# CONNECTOR_B.net
KiCad netlist of a schematic drawn in Altium Designer
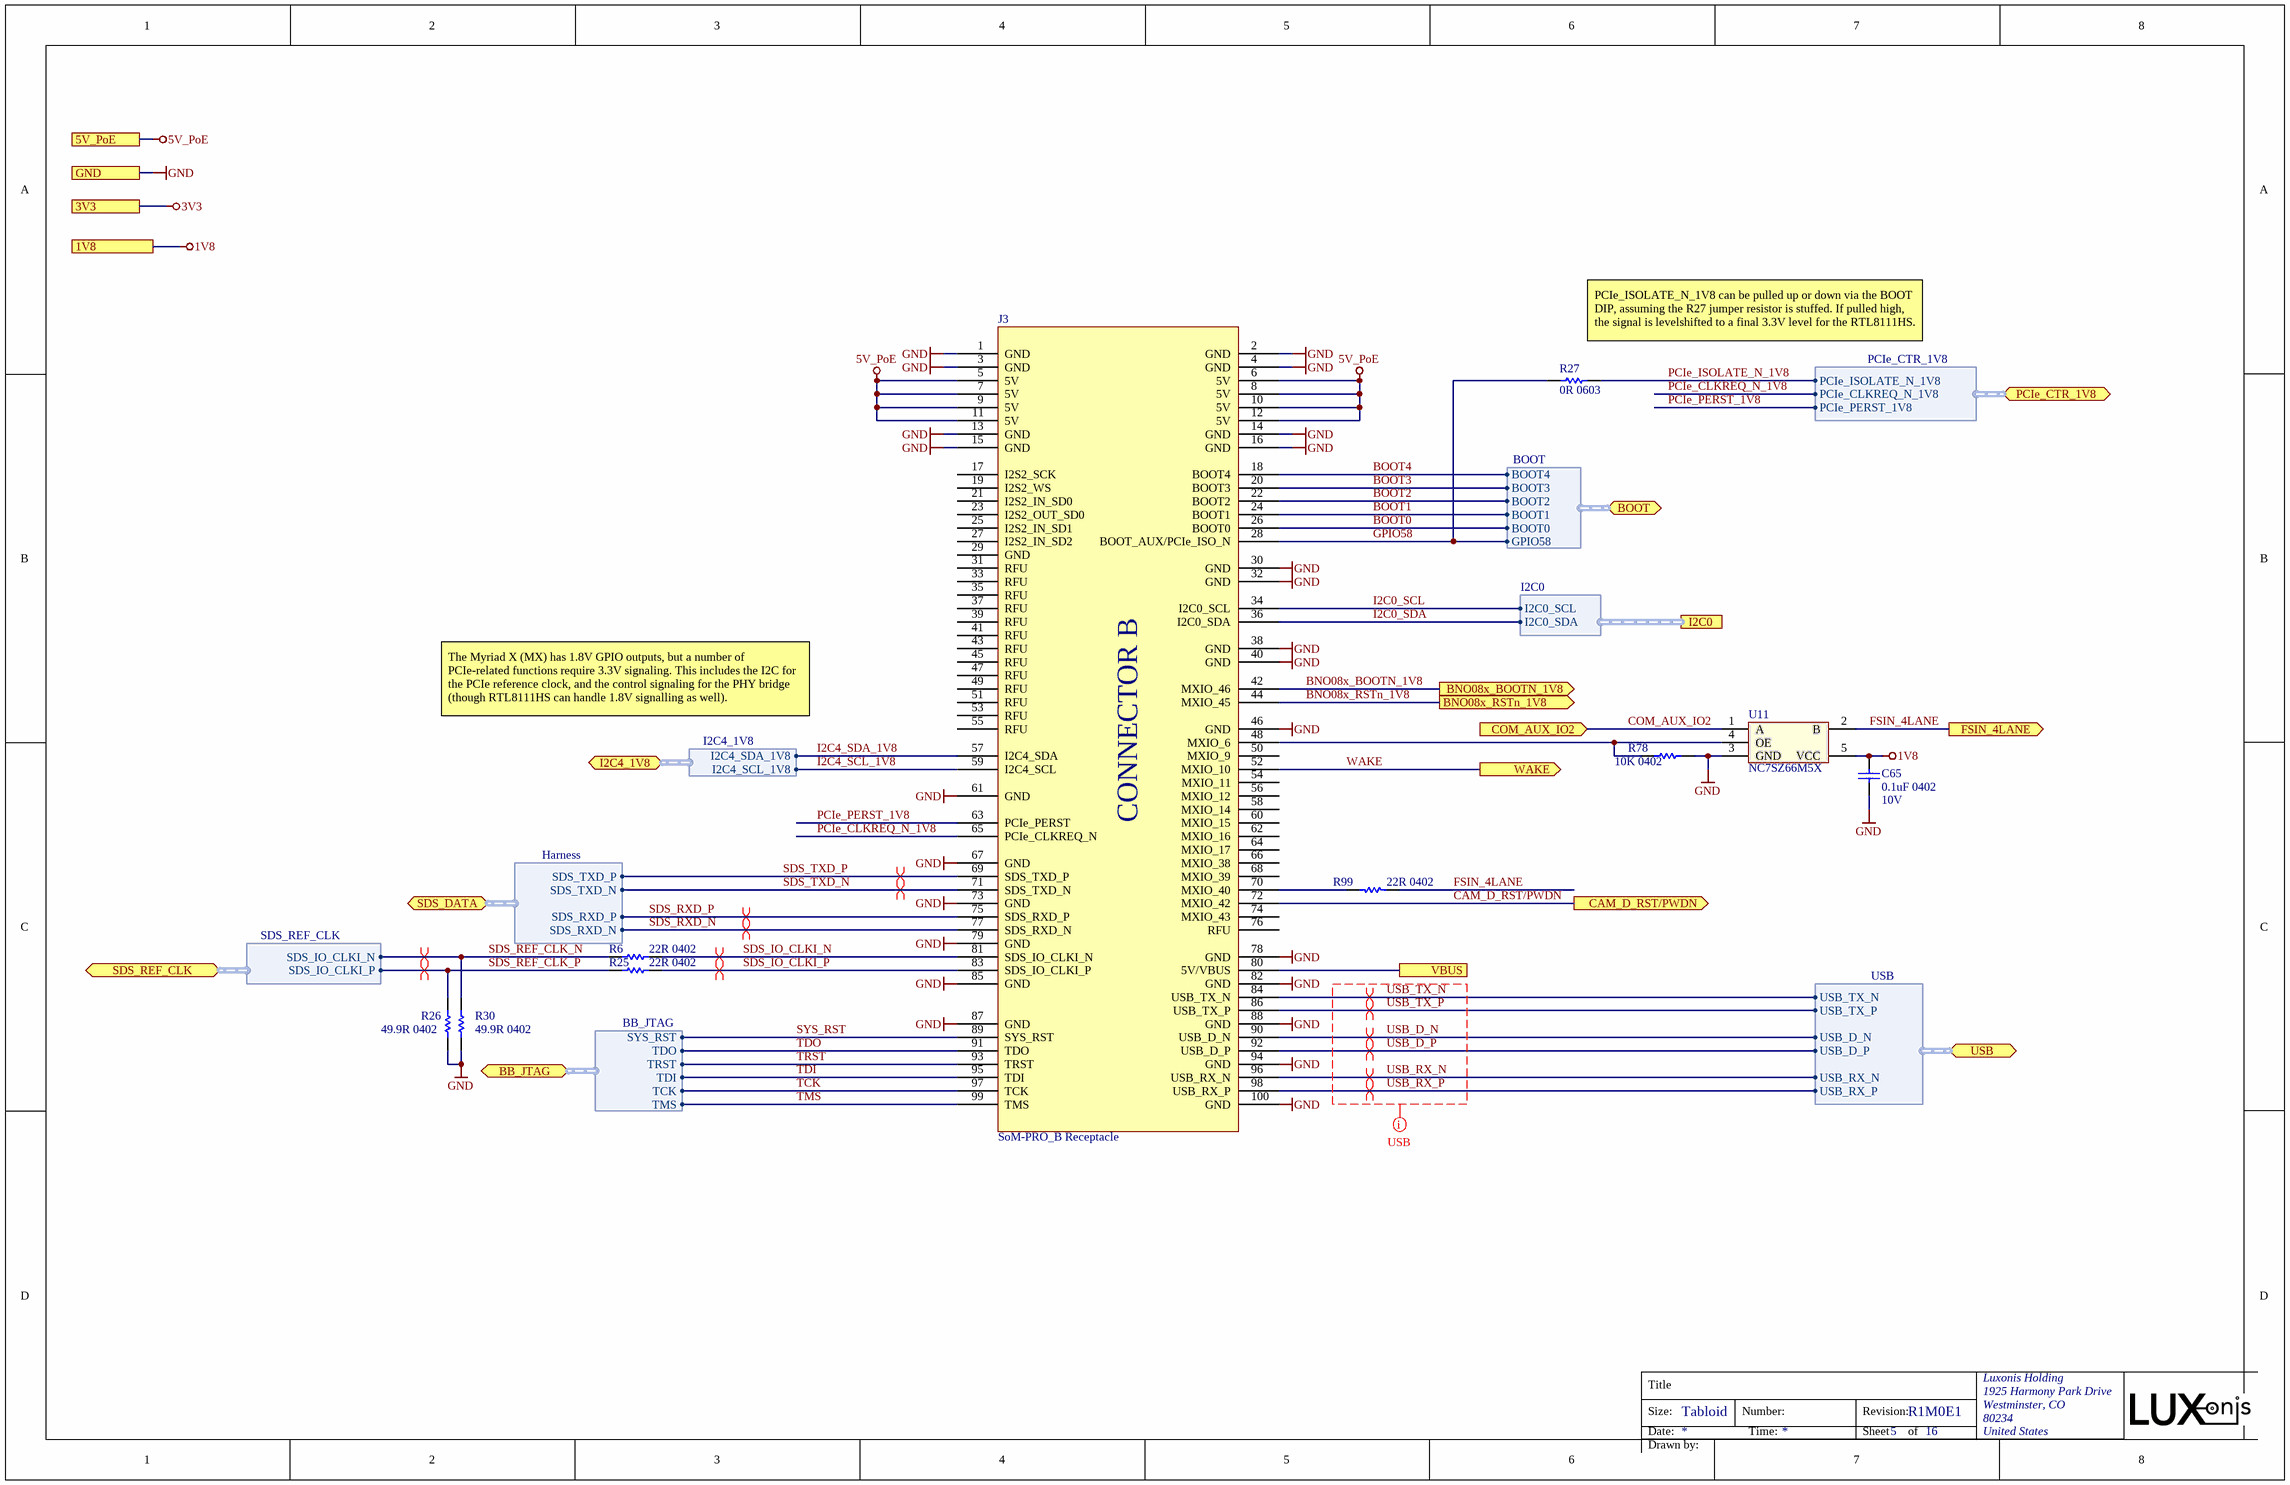
[diagram p0: CONNECTOR_B.SchDoc]

(export (version "E")
  (design (tool "Eeschema 10.0.6"))
  (components
    (comp (ref "C65")
      (value "0.1uF 0402")
      (footprint "CAPC0402(1005)70_L")
      (description "CAP CER 0.1UF 10V X7R 0402 5%")
      (fields (field (name "TOLERANCE") "5%") (field (name "VOLTAGE RATING") "10V"))
      (libsource (lib "LuxonisMaster") (part "GRM155R71A104JA01D"))
    )
    (comp (ref "J3")
      (value "SoM-PRO_B Receptacle")
      (footprint "LuxonisMaster:CON_B_BW2099_SoM_DF40HC-3.0-100DS-0.4V_minpad")
      (description "CONN RCPT 100POS 0.4MM SMD GOLD")
      (libsource (lib "LuxonisMaster") (part "DF40HC(3.0)-100DS-0.4V_SoM-PRO_B"))
    )
    (comp (ref "R6")
      (value "22R 0402")
      (footprint "RES_Altium_Vault_Generic:RESC0402(1005)_L")
      (description "RES SMD 22 OHM 1% 1/16W 0402")
      (fields (field (name "TOLERANCE") "1%"))
      (libsource (lib "BW2098POE") (part "RC0402FR-0722RL"))
    )
    (comp (ref "R25")
      (value "22R 0402")
      (footprint "RES_Altium_Vault_Generic:RESC0402(1005)_L")
      (description "RES SMD 22 OHM 1% 1/16W 0402")
      (fields (field (name "TOLERANCE") "1%"))
      (libsource (lib "BW2098POE") (part "RC0402FR-0722RL"))
    )
    (comp (ref "R26")
      (value "49.9R 0402")
      (footprint "RES_Altium_Vault_Generic:RESC0402(1005)_L")
      (description "RES SMD 49.9 OHM 1% 1/16W 0402")
      (fields (field (name "TOLERANCE") "1%"))
      (libsource (lib "LuxonisMaster") (part "RC0402FR-0749R9L"))
    )
    (comp (ref "R27")
      (value "0R 0603")
      (footprint "RESC0603(1608)_N")
      (fields (field (name "TOLERANCE") "5%"))
      (libsource (lib "LuxonisMaster") (part "CRCW06030000Z0EA"))
    )
    (comp (ref "R30")
      (value "49.9R 0402")
      (footprint "RES_Altium_Vault_Generic:RESC0402(1005)_L")
      (description "RES SMD 49.9 OHM 1% 1/16W 0402")
      (fields (field (name "TOLERANCE") "1%"))
      (libsource (lib "LuxonisMaster") (part "RC0402FR-0749R9L"))
    )
    (comp (ref "R78")
      (value "10K 0402")
      (footprint "RESC0402(1005)_L")
      (fields (field (name "TOLERANCE") "1%"))
      (libsource (lib "LuxonisMaster") (part "RC0402FR-1310KL"))
    )
    (comp (ref "R99")
      (value "22R 0402")
      (footprint "RES_Altium_Vault_Generic:RESC0402(1005)_L")
      (description "RES SMD 22 OHM 1% 1/16W 0402")
      (fields (field (name "TOLERANCE") "1%"))
      (libsource (lib "BW2098POE") (part "RC0402FR-0722RL"))
    )
    (comp (ref "U11")
      (value "NC7SZ66M5X")
      (footprint "SOT235")
      (fields (field (name "VOLTAGE") "5V"))
      (libsource (lib "DD2099_4CAM_FFC") (part "NC7SZ66M5X"))
    )
  )
  (nets
    (net (code "9") (name "/BNO08x_BOOTN_1V8") (class "Default")
      (node (ref "J3") (pin "42") (pinfunction "MXIO_46_42") (pintype "passive"))
    )
    (net (code "10") (name "/BNO08x_RSTn_1V8") (class "Default")
      (node (ref "J3") (pin "44") (pinfunction "MXIO_45_44") (pintype "passive"))
    )
    (net (code "11") (name "/BOOT0") (class "Default")
      (node (ref "J3") (pin "26") (pinfunction "BOOT0_26") (pintype "passive"))
    )
    (net (code "12") (name "/BOOT1") (class "Default")
      (node (ref "J3") (pin "24") (pinfunction "BOOT1_24") (pintype "passive"))
    )
    (net (code "13") (name "/BOOT2") (class "Default")
      (node (ref "J3") (pin "22") (pinfunction "BOOT2_22") (pintype "passive"))
    )
    (net (code "14") (name "/BOOT3") (class "Default")
      (node (ref "J3") (pin "20") (pinfunction "BOOT3_20") (pintype "passive"))
    )
    (net (code "15") (name "/BOOT4") (class "Default")
      (node (ref "J3") (pin "18") (pinfunction "BOOT4_18") (pintype "passive"))
    )
    (net (code "16") (name "/CAM_D_RST{slash}PWDN") (class "Default")
      (node (ref "J3") (pin "72") (pinfunction "MXIO_42_72") (pintype "passive"))
    )
    (net (code "17") (name "/COM_AUX_IO2") (class "Default")
      (node (ref "U11") (pin "1") (pinfunction "A_1") (pintype "passive"))
    )
    (net (code "18") (name "/FSIN_4LANE") (class "Default")
      (node (ref "R99") (pin "1") (pinfunction "1_1") (pintype "passive"))
      (node (ref "U11") (pin "2") (pinfunction "B_2") (pintype "passive"))
    )
    (net (code "19") (name "/GPIO58") (class "Default")
      (node (ref "J3") (pin "28") (pinfunction "BOOT_AUX/PCIe_ISO_N_28") (pintype "passive"))
      (node (ref "R27") (pin "1") (pinfunction "1_1") (pintype "passive"))
    )
    (net (code "20") (name "/I2C0_SCL") (class "Default")
      (node (ref "J3") (pin "34") (pinfunction "I2C0_SCL_34") (pintype "passive"))
    )
    (net (code "21") (name "/I2C0_SDA") (class "Default")
      (node (ref "J3") (pin "36") (pinfunction "I2C0_SDA_36") (pintype "passive"))
    )
    (net (code "22") (name "/I2C4_SCL_1V8") (class "Default")
      (node (ref "J3") (pin "59") (pinfunction "I2C4_SCL_59") (pintype "passive"))
    )
    (net (code "23") (name "/I2C4_SDA_1V8") (class "Default")
      (node (ref "J3") (pin "57") (pinfunction "I2C4_SDA_57") (pintype "passive"))
    )
    (net (code "24") (name "/PCIe_CLKREQ_N_1V8") (class "Default")
      (node (ref "J3") (pin "65") (pinfunction "PCIe_CLKREQ_N_65") (pintype "passive"))
    )
    (net (code "25") (name "/PCIe_ISOLATE_N_1V8") (class "Default")
      (node (ref "R27") (pin "2") (pinfunction "2_2") (pintype "passive"))
    )
    (net (code "26") (name "/PCIe_PERST_1V8") (class "Default")
      (node (ref "J3") (pin "63") (pinfunction "PCIe_PERST_63") (pintype "passive"))
    )
    (net (code "27") (name "/SDS_IO_CLKI_N") (class "Default")
      (node (ref "J3") (pin "81") (pinfunction "SDS_IO_CLKI_N_81") (pintype "passive"))
      (node (ref "R6") (pin "2") (pinfunction "2_2") (pintype "passive"))
    )
    (net (code "28") (name "/SDS_IO_CLKI_P") (class "Default")
      (node (ref "J3") (pin "83") (pinfunction "SDS_IO_CLKI_P_83") (pintype "passive"))
      (node (ref "R25") (pin "2") (pinfunction "2_2") (pintype "passive"))
    )
    (net (code "29") (name "/SDS_REF_CLK_N") (class "Default")
      (node (ref "R30") (pin "1") (pinfunction "1_1") (pintype "passive"))
      (node (ref "R6") (pin "1") (pinfunction "1_1") (pintype "passive"))
    )
    (net (code "30") (name "/SDS_REF_CLK_P") (class "Default")
      (node (ref "R25") (pin "1") (pinfunction "1_1") (pintype "passive"))
      (node (ref "R26") (pin "2") (pinfunction "2_2") (pintype "passive"))
    )
    (net (code "31") (name "/SDS_RXD_N") (class "Default")
      (node (ref "J3") (pin "77") (pinfunction "SDS_RXD_N_77") (pintype "passive"))
    )
    (net (code "32") (name "/SDS_RXD_P") (class "Default")
      (node (ref "J3") (pin "75") (pinfunction "SDS_RXD_P_75") (pintype "passive"))
    )
    (net (code "33") (name "/SDS_TXD_N") (class "Default")
      (node (ref "J3") (pin "71") (pinfunction "SDS_TXD_N_71") (pintype "passive"))
    )
    (net (code "34") (name "/SDS_TXD_P") (class "Default")
      (node (ref "J3") (pin "69") (pinfunction "SDS_TXD_P_69") (pintype "passive"))
    )
    (net (code "35") (name "/SYS_RST") (class "Default")
      (node (ref "J3") (pin "89") (pinfunction "SYS_RST_89") (pintype "passive"))
    )
    (net (code "36") (name "/TCK") (class "Default")
      (node (ref "J3") (pin "97") (pinfunction "TCK_97") (pintype "passive"))
    )
    (net (code "37") (name "/TDI") (class "Default")
      (node (ref "J3") (pin "95") (pinfunction "TDI_95") (pintype "passive"))
    )
    (net (code "38") (name "/TDO") (class "Default")
      (node (ref "J3") (pin "91") (pinfunction "TDO_91") (pintype "passive"))
    )
    (net (code "39") (name "/TMS") (class "Default")
      (node (ref "J3") (pin "99") (pinfunction "TMS_99") (pintype "passive"))
    )
    (net (code "40") (name "/TRST") (class "Default")
      (node (ref "J3") (pin "93") (pinfunction "TRST_93") (pintype "passive"))
    )
    (net (code "41") (name "/USB_D_N") (class "Default")
      (node (ref "J3") (pin "90") (pinfunction "USB_D_N_90") (pintype "passive"))
    )
    (net (code "42") (name "/USB_D_P") (class "Default")
      (node (ref "J3") (pin "92") (pinfunction "USB_D_P_92") (pintype "passive"))
    )
    (net (code "43") (name "/USB_RX_N") (class "Default")
      (node (ref "J3") (pin "96") (pinfunction "USB_RX_N_96") (pintype "passive"))
    )
    (net (code "44") (name "/USB_RX_P") (class "Default")
      (node (ref "J3") (pin "98") (pinfunction "USB_RX_P_98") (pintype "passive"))
    )
    (net (code "45") (name "/USB_TX_N") (class "Default")
      (node (ref "J3") (pin "84") (pinfunction "USB_TX_N_84") (pintype "passive"))
    )
    (net (code "46") (name "/USB_TX_P") (class "Default")
      (node (ref "J3") (pin "86") (pinfunction "USB_TX_P_86") (pintype "passive"))
    )
    (net (code "47") (name "/VBUS") (class "Default")
      (node (ref "J3") (pin "80") (pinfunction "5V/VBUS_80") (pintype "passive"))
    )
    (net (code "48") (name "/WAKE") (class "Default")
      (node (ref "J3") (pin "52") (pinfunction "MXIO_10_52") (pintype "passive"))
    )
    (net (code "57") (name "1V8") (class "Default")
      (node (ref "C65") (pin "2") (pinfunction "2_2") (pintype "passive"))
      (node (ref "U11") (pin "5") (pinfunction "VCC_5") (pintype "passive"))
    )
    (net (code "59") (name "5V_PoE") (class "Default")
      (node (ref "J3") (pin "10") (pinfunction "5V_10") (pintype "passive"))
      (node (ref "J3") (pin "11") (pinfunction "5V_11") (pintype "passive"))
      (node (ref "J3") (pin "12") (pinfunction "5V_12") (pintype "passive"))
      (node (ref "J3") (pin "5") (pinfunction "5V_5") (pintype "passive"))
      (node (ref "J3") (pin "6") (pinfunction "5V_6") (pintype "passive"))
      (node (ref "J3") (pin "7") (pinfunction "5V_7") (pintype "passive"))
      (node (ref "J3") (pin "8") (pinfunction "5V_8") (pintype "passive"))
      (node (ref "J3") (pin "9") (pinfunction "5V_9") (pintype "passive"))
    )
    (net (code "60") (name "GND") (class "Default")
      (node (ref "C65") (pin "1") (pinfunction "1_1") (pintype "passive"))
      (node (ref "J3") (pin "1") (pinfunction "GND_1") (pintype "passive"))
      (node (ref "J3") (pin "100") (pinfunction "GND_100") (pintype "passive"))
      (node (ref "J3") (pin "13") (pinfunction "GND_13") (pintype "passive"))
      (node (ref "J3") (pin "14") (pinfunction "GND_14") (pintype "passive"))
      (node (ref "J3") (pin "15") (pinfunction "GND_15") (pintype "passive"))
      (node (ref "J3") (pin "16") (pinfunction "GND_16") (pintype "passive"))
      (node (ref "J3") (pin "2") (pinfunction "GND_2") (pintype "passive"))
      (node (ref "J3") (pin "3") (pinfunction "GND_3") (pintype "passive"))
      (node (ref "J3") (pin "30") (pinfunction "GND_30") (pintype "passive"))
      (node (ref "J3") (pin "32") (pinfunction "GND_32") (pintype "passive"))
      (node (ref "J3") (pin "38") (pinfunction "GND_38") (pintype "passive"))
      (node (ref "J3") (pin "4") (pinfunction "GND_4") (pintype "passive"))
      (node (ref "J3") (pin "40") (pinfunction "GND_40") (pintype "passive"))
      (node (ref "J3") (pin "46") (pinfunction "GND_46") (pintype "passive"))
      (node (ref "J3") (pin "61") (pinfunction "GND_61") (pintype "passive"))
      (node (ref "J3") (pin "67") (pinfunction "GND_67") (pintype "passive"))
      (node (ref "J3") (pin "73") (pinfunction "GND_73") (pintype "passive"))
      (node (ref "J3") (pin "78") (pinfunction "GND_78") (pintype "passive"))
      (node (ref "J3") (pin "79") (pinfunction "GND_79") (pintype "passive"))
      (node (ref "J3") (pin "82") (pinfunction "GND_82") (pintype "passive"))
      (node (ref "J3") (pin "85") (pinfunction "GND_85") (pintype "passive"))
      (node (ref "J3") (pin "87") (pinfunction "GND_87") (pintype "passive"))
      (node (ref "J3") (pin "88") (pinfunction "GND_88") (pintype "passive"))
      (node (ref "J3") (pin "94") (pinfunction "GND_94") (pintype "passive"))
      (node (ref "R26") (pin "1") (pinfunction "1_1") (pintype "passive"))
      (node (ref "R30") (pin "2") (pinfunction "2_2") (pintype "passive"))
      (node (ref "R78") (pin "1") (pinfunction "1_1") (pintype "passive"))
      (node (ref "U11") (pin "3") (pinfunction "GND_3") (pintype "passive"))
    )
    (net (code "61") (name "Net-(J3-MXIO_6)") (class "Default")
      (node (ref "J3") (pin "48") (pinfunction "MXIO_6_48") (pintype "passive"))
      (node (ref "R78") (pin "2") (pinfunction "2_2") (pintype "passive"))
      (node (ref "U11") (pin "4") (pinfunction "OE_4") (pintype "passive"))
    )
    (net (code "62") (name "Net-(J3-MXIO_40)") (class "Default")
      (node (ref "J3") (pin "70") (pinfunction "MXIO_40_70") (pintype "passive"))
      (node (ref "R99") (pin "2") (pinfunction "2_2") (pintype "passive"))
    )
    (net (code "63") (name "unconnected-(J3-GND-Pad29)") (class "Default")
      (node (ref "J3") (pin "29") (pinfunction "GND_29") (pintype "passive"))
    )
    (net (code "64") (name "unconnected-(J3-I2S2_IN_SD0-Pad21)") (class "Default")
      (node (ref "J3") (pin "21") (pinfunction "I2S2_IN_SD0_21") (pintype "passive"))
    )
    (net (code "65") (name "unconnected-(J3-I2S2_IN_SD1-Pad25)") (class "Default")
      (node (ref "J3") (pin "25") (pinfunction "I2S2_IN_SD1_25") (pintype "passive"))
    )
    (net (code "66") (name "unconnected-(J3-I2S2_IN_SD2-Pad27)") (class "Default")
      (node (ref "J3") (pin "27") (pinfunction "I2S2_IN_SD2_27") (pintype "passive"))
    )
    (net (code "67") (name "unconnected-(J3-I2S2_OUT_SD0-Pad23)") (class "Default")
      (node (ref "J3") (pin "23") (pinfunction "I2S2_OUT_SD0_23") (pintype "passive"))
    )
    (net (code "68") (name "unconnected-(J3-I2S2_SCK-Pad17)") (class "Default")
      (node (ref "J3") (pin "17") (pinfunction "I2S2_SCK_17") (pintype "passive"))
    )
    (net (code "69") (name "unconnected-(J3-I2S2_WS-Pad19)") (class "Default")
      (node (ref "J3") (pin "19") (pinfunction "I2S2_WS_19") (pintype "passive"))
    )
    (net (code "70") (name "unconnected-(J3-MXIO_9-Pad50)") (class "Default")
      (node (ref "J3") (pin "50") (pinfunction "MXIO_9_50") (pintype "passive"))
    )
    (net (code "71") (name "unconnected-(J3-MXIO_11-Pad54)") (class "Default")
      (node (ref "J3") (pin "54") (pinfunction "MXIO_11_54") (pintype "passive"))
    )
    (net (code "72") (name "unconnected-(J3-MXIO_12-Pad56)") (class "Default")
      (node (ref "J3") (pin "56") (pinfunction "MXIO_12_56") (pintype "passive"))
    )
    (net (code "73") (name "unconnected-(J3-MXIO_14-Pad58)") (class "Default")
      (node (ref "J3") (pin "58") (pinfunction "MXIO_14_58") (pintype "passive"))
    )
    (net (code "74") (name "unconnected-(J3-MXIO_15-Pad60)") (class "Default")
      (node (ref "J3") (pin "60") (pinfunction "MXIO_15_60") (pintype "passive"))
    )
    (net (code "75") (name "unconnected-(J3-MXIO_16-Pad62)") (class "Default")
      (node (ref "J3") (pin "62") (pinfunction "MXIO_16_62") (pintype "passive"))
    )
    (net (code "76") (name "unconnected-(J3-MXIO_17-Pad64)") (class "Default")
      (node (ref "J3") (pin "64") (pinfunction "MXIO_17_64") (pintype "passive"))
    )
    (net (code "77") (name "unconnected-(J3-MXIO_38-Pad66)") (class "Default")
      (node (ref "J3") (pin "66") (pinfunction "MXIO_38_66") (pintype "passive"))
    )
    (net (code "78") (name "unconnected-(J3-MXIO_39-Pad68)") (class "Default")
      (node (ref "J3") (pin "68") (pinfunction "MXIO_39_68") (pintype "passive"))
    )
    (net (code "79") (name "unconnected-(J3-MXIO_43-Pad74)") (class "Default")
      (node (ref "J3") (pin "74") (pinfunction "MXIO_43_74") (pintype "passive"))
    )
    (net (code "80") (name "unconnected-(J3-RFU-Pad31)") (class "Default")
      (node (ref "J3") (pin "31") (pinfunction "RFU_31") (pintype "passive"))
    )
    (net (code "81") (name "unconnected-(J3-RFU-Pad33)") (class "Default")
      (node (ref "J3") (pin "33") (pinfunction "RFU_33") (pintype "passive"))
    )
    (net (code "82") (name "unconnected-(J3-RFU-Pad35)") (class "Default")
      (node (ref "J3") (pin "35") (pinfunction "RFU_35") (pintype "passive"))
    )
    (net (code "83") (name "unconnected-(J3-RFU-Pad37)") (class "Default")
      (node (ref "J3") (pin "37") (pinfunction "RFU_37") (pintype "passive"))
    )
    (net (code "84") (name "unconnected-(J3-RFU-Pad39)") (class "Default")
      (node (ref "J3") (pin "39") (pinfunction "RFU_39") (pintype "passive"))
    )
    (net (code "85") (name "unconnected-(J3-RFU-Pad41)") (class "Default")
      (node (ref "J3") (pin "41") (pinfunction "RFU_41") (pintype "passive"))
    )
    (net (code "86") (name "unconnected-(J3-RFU-Pad43)") (class "Default")
      (node (ref "J3") (pin "43") (pinfunction "RFU_43") (pintype "passive"))
    )
    (net (code "87") (name "unconnected-(J3-RFU-Pad45)") (class "Default")
      (node (ref "J3") (pin "45") (pinfunction "RFU_45") (pintype "passive"))
    )
    (net (code "88") (name "unconnected-(J3-RFU-Pad47)") (class "Default")
      (node (ref "J3") (pin "47") (pinfunction "RFU_47") (pintype "passive"))
    )
    (net (code "89") (name "unconnected-(J3-RFU-Pad49)") (class "Default")
      (node (ref "J3") (pin "49") (pinfunction "RFU_49") (pintype "passive"))
    )
    (net (code "90") (name "unconnected-(J3-RFU-Pad51)") (class "Default")
      (node (ref "J3") (pin "51") (pinfunction "RFU_51") (pintype "passive"))
    )
    (net (code "91") (name "unconnected-(J3-RFU-Pad53)") (class "Default")
      (node (ref "J3") (pin "53") (pinfunction "RFU_53") (pintype "passive"))
    )
    (net (code "92") (name "unconnected-(J3-RFU-Pad55)") (class "Default")
      (node (ref "J3") (pin "55") (pinfunction "RFU_55") (pintype "passive"))
    )
    (net (code "93") (name "unconnected-(J3-RFU-Pad76)") (class "Default")
      (node (ref "J3") (pin "76") (pinfunction "RFU_76") (pintype "passive"))
    )
  )
)
